# COMMUNICATION.net
KiCad netlist of a schematic drawn in Altium Designer
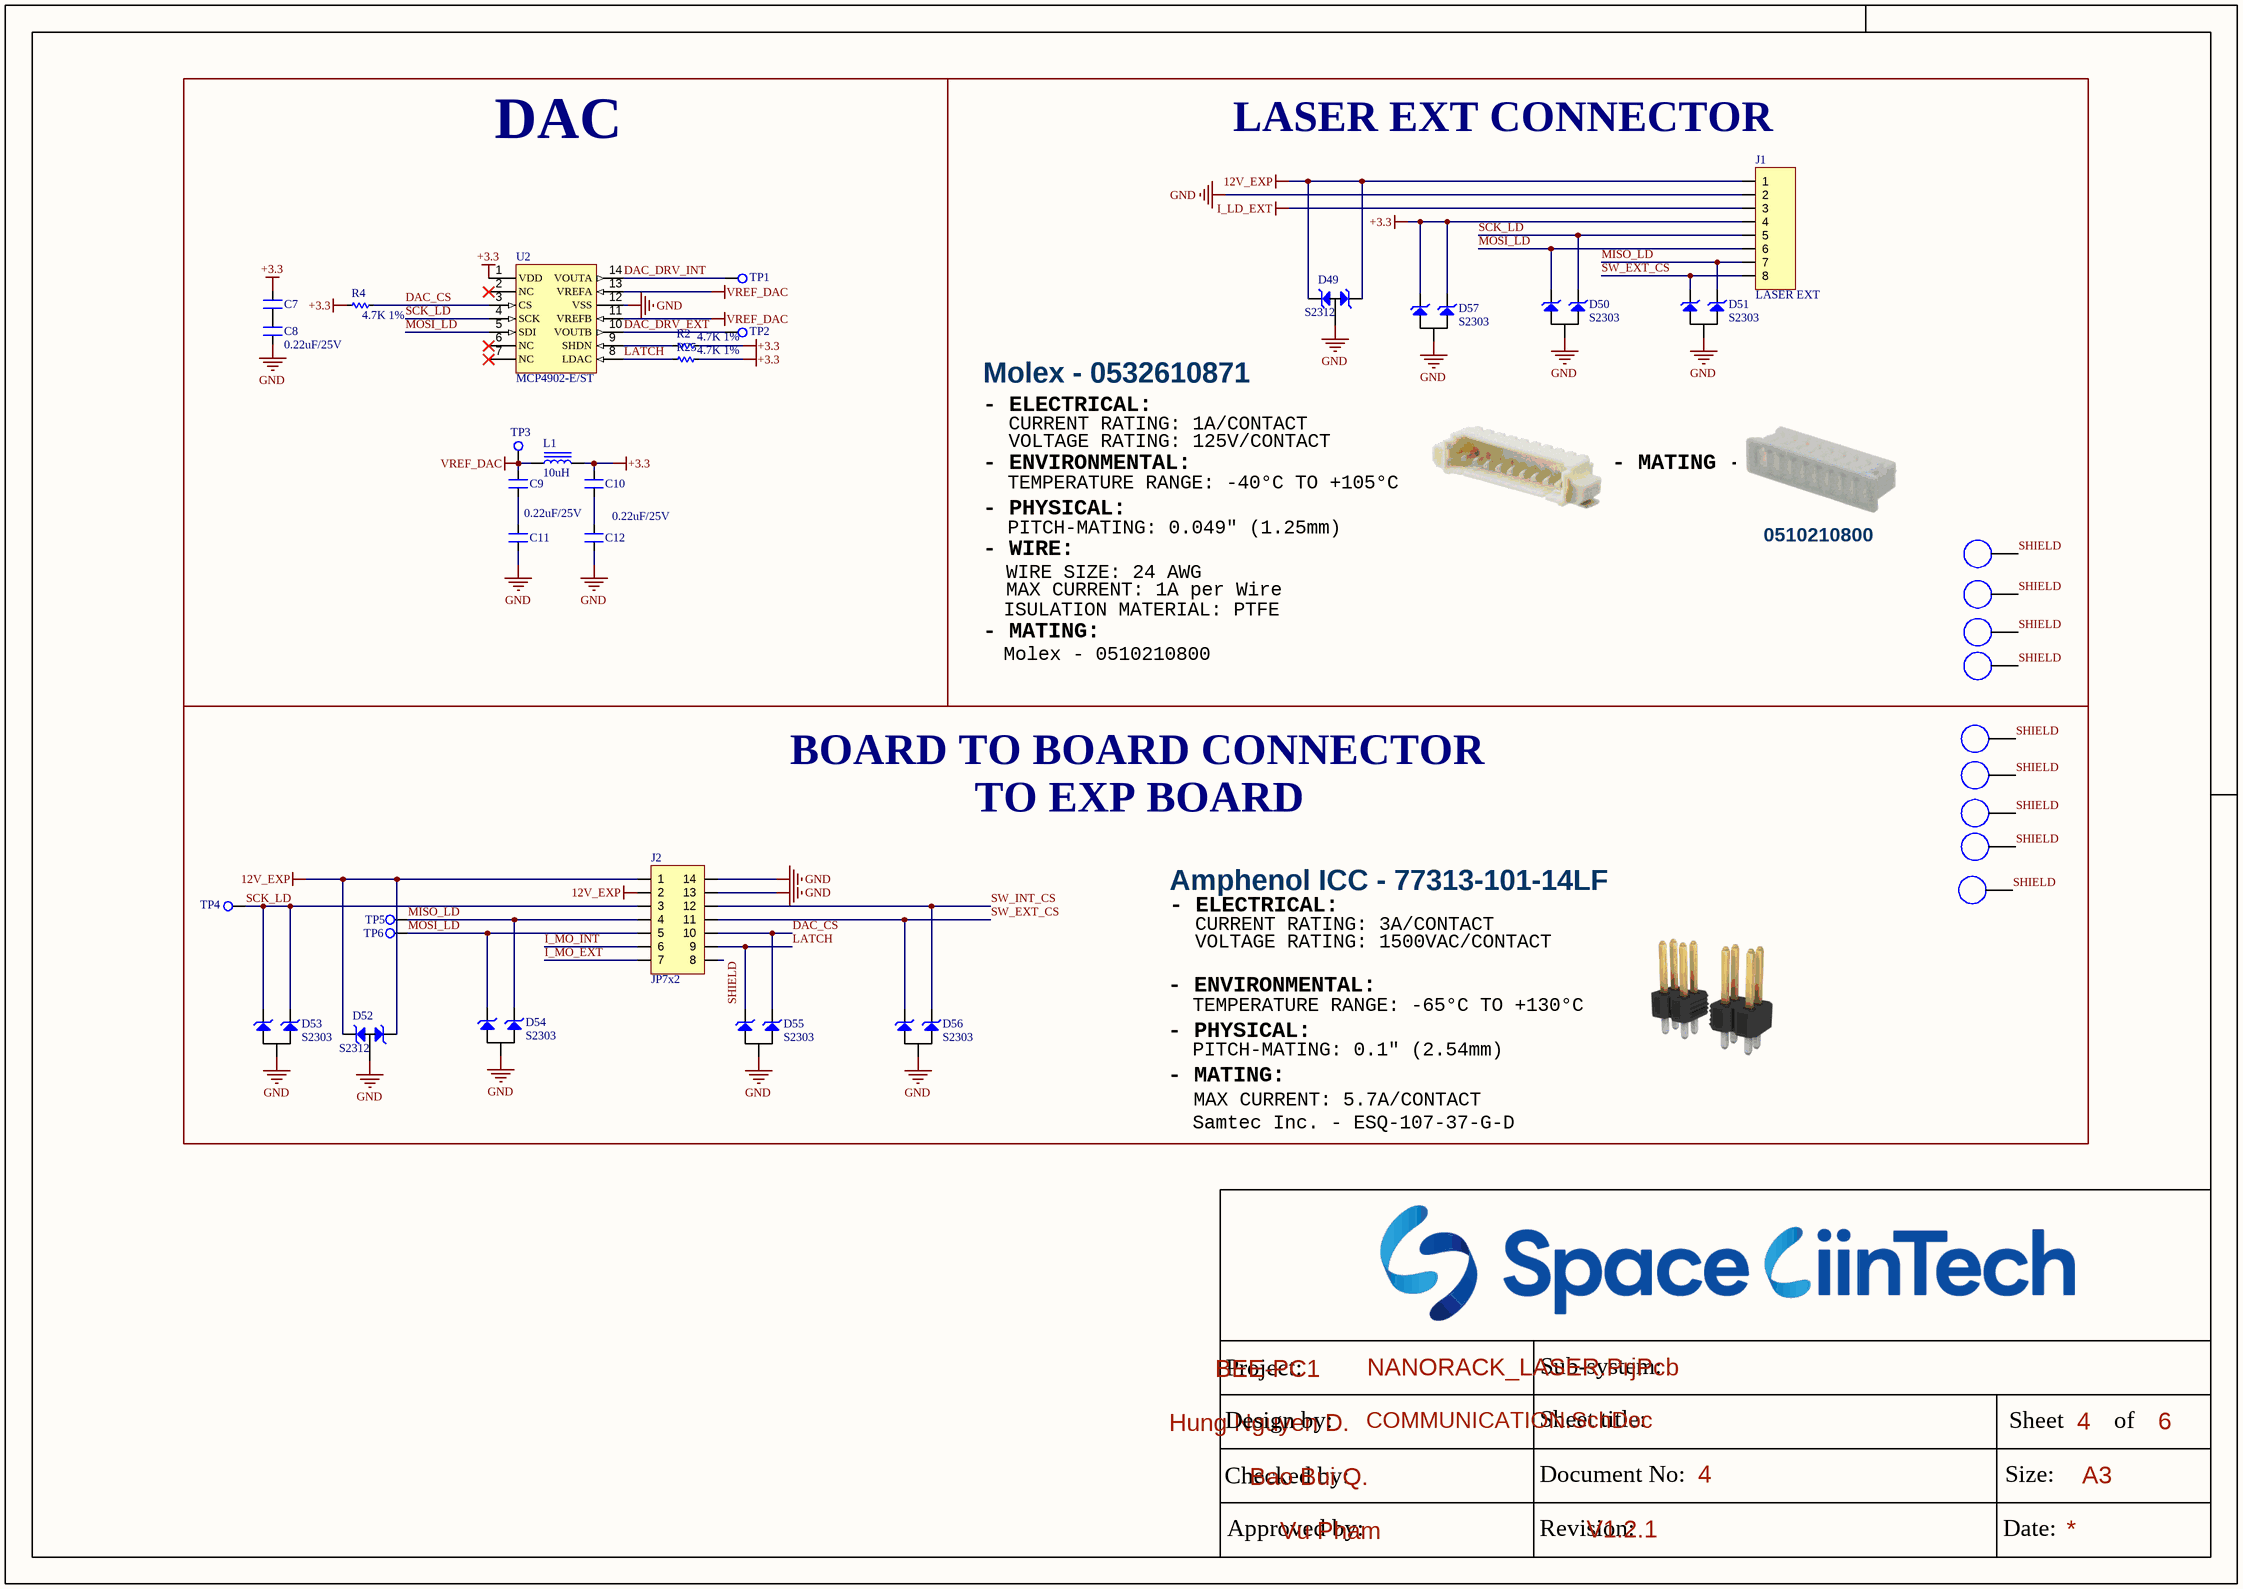
[diagram p0: COMMUNICATION.SchDoc]

(export (version "E")
  (design (tool "Eeschema 10.0.6"))
  (components
    (comp (ref "C7")
      (value "0.22uF/25V")
      (footprint "SM-0603")
      (description "0603")
      (libsource (lib "Capacitors") (part "CM"))
    )
    (comp (ref "C8")
      (value "0.22uF/25V")
      (footprint "SM-0603")
      (description "0603")
      (libsource (lib "Capacitors") (part "CM"))
    )
    (comp (ref "C9")
      (value "0.22uF/25V")
      (footprint "SM-0603")
      (description "0603")
      (libsource (lib "Capacitors") (part "CM"))
    )
    (comp (ref "C10")
      (value "0.22uF/25V")
      (footprint "SM-0603")
      (description "0603")
      (libsource (lib "Capacitors") (part "CM"))
    )
    (comp (ref "C11")
      (value "0.22uF/25V")
      (footprint "SM-0603")
      (description "0603")
      (libsource (lib "Capacitors") (part "CM"))
    )
    (comp (ref "C12")
      (value "0.22uF/25V")
      (footprint "SM-0603")
      (description "0603")
      (libsource (lib "Capacitors") (part "CM"))
    )
    (comp (ref "D49")
      (value "S2312")
      (footprint "SOT23-123")
      (description "TVS DIODE 12VWM 19VC SOT23, P/N:  S2312")
      (libsource (lib "Library") (part "S2315"))
    )
    (comp (ref "D50")
      (value "S2303")
      (footprint "SOT23-123")
      (description "TVS DIODE 3.3VWM 8VC SOT23, P/N:  \r\nS2303")
      (libsource (lib "Library") (part "S2303"))
    )
    (comp (ref "D51")
      (value "S2303")
      (footprint "SOT23-123")
      (description "TVS DIODE 3.3VWM 8VC SOT23, P/N:  \r\nS2303")
      (libsource (lib "Library") (part "S2303"))
    )
    (comp (ref "D52")
      (value "S2312")
      (footprint "SOT23-123")
      (description "TVS DIODE 12VWM 19VC SOT23, P/N:  S2312")
      (libsource (lib "Library") (part "S2315"))
    )
    (comp (ref "D53")
      (value "S2303")
      (footprint "SOT23-123")
      (description "TVS DIODE 3.3VWM 8VC SOT23, P/N:  \r\nS2303")
      (libsource (lib "Library") (part "S2303"))
    )
    (comp (ref "D54")
      (value "S2303")
      (footprint "SOT23-123")
      (description "TVS DIODE 3.3VWM 8VC SOT23, P/N:  \r\nS2303")
      (libsource (lib "Library") (part "S2303"))
    )
    (comp (ref "D55")
      (value "S2303")
      (footprint "SOT23-123")
      (description "TVS DIODE 3.3VWM 8VC SOT23, P/N:  \r\nS2303")
      (libsource (lib "Library") (part "S2303"))
    )
    (comp (ref "D56")
      (value "S2303")
      (footprint "SOT23-123")
      (description "TVS DIODE 3.3VWM 8VC SOT23, P/N:  \r\nS2303")
      (libsource (lib "Library") (part "S2303"))
    )
    (comp (ref "D57")
      (value "S2303")
      (footprint "SOT23-123")
      (description "TVS DIODE 3.3VWM 8VC SOT23, P/N:  \r\nS2303")
      (libsource (lib "Library") (part "S2303"))
    )
    (comp (ref "H1") (value "HOLD") (footprint "M3") (libsource (lib "Library_HUNG") (part "PAD_HOLD")))
    (comp (ref "H2") (value "HOLD") (footprint "M3") (libsource (lib "Library_HUNG") (part "PAD_HOLD")))
    (comp (ref "H3") (value "HOLD") (footprint "M3") (libsource (lib "Library_HUNG") (part "PAD_HOLD")))
    (comp (ref "H4") (value "HOLD") (footprint "M3") (libsource (lib "Library_HUNG") (part "PAD_HOLD")))
    (comp (ref "H5") (value "HOLD") (footprint "M3") (libsource (lib "Library_HUNG") (part "PAD_HOLD")))
    (comp (ref "H6") (value "HOLD") (footprint "M3") (libsource (lib "Library_HUNG") (part "PAD_HOLD")))
    (comp (ref "H7") (value "HOLD") (footprint "M3") (libsource (lib "Library_HUNG") (part "PAD_HOLD")))
    (comp (ref "H8") (value "HOLD") (footprint "M3") (libsource (lib "Library_HUNG") (part "PAD_HOLD")))
    (comp (ref "H9") (value "HOLD") (footprint "M3") (libsource (lib "Library_HUNG") (part "PAD_HOLD")))
    (comp (ref "J1")
      (value "LASER EXT")
      (footprint "0532610871")
      (description "WR-PHD 2.54 mm Angled Socket Header")
      (fields
        (field (name "MANUFACTURER") "Würth Elektronik eiSos GmbH")
        (field (name "PARTNO") "613008143121")
        (field (name "CREATED BY") "Karrer Zheng")
      )
      (libsource (lib "Library_HUNG") (part "JP8"))
    )
    (comp (ref "J2")
      (value "JP7x2")
      (footprint "JP7-D2T")
      (description "WR-PHD 2.54 mm Dual Socket Header")
      (fields
        (field (name "MANUFACTURER") "Würth Elektronik eiSos GmbH")
        (field (name "PARTNO") "61301421821")
        (field (name "CREATED BY") "Karrer Zheng")
      )
      (libsource (lib "Library") (part "JP7x2"))
    )
    (comp (ref "L1")
      (value "10uH")
      (footprint "FER 0805/2012")
      (description "MLZ1608N100LT000")
      (libsource (lib "INDUCTOR") (part "Inductor"))
    )
    (comp (ref "R2")
      (value "4.7K 1%")
      (footprint "RES-SMD-0603")
      (description "0603")
      (fields
        (field (name "MANUFACTURER") "Generic Components")
        (field (name "PUBLISHER") "Altium Hobart Technology Centre")
      )
      (libsource (lib "Library") (part "Res-SMD"))
    )
    (comp (ref "R4")
      (value "4.7K 1%")
      (footprint "RES-SMD-0603")
      (description "0603")
      (fields
        (field (name "MANUFACTURER") "Generic Components")
        (field (name "PUBLISHER") "Altium Hobart Technology Centre")
      )
      (libsource (lib "Library") (part "Res-SMD"))
    )
    (comp (ref "R25")
      (value "4.7K 1%")
      (footprint "RES-SMD-0603")
      (description "0603")
      (fields
        (field (name "MANUFACTURER") "Generic Components")
        (field (name "PUBLISHER") "Altium Hobart Technology Centre")
      )
      (libsource (lib "Library") (part "Res-SMD"))
    )
    (comp (ref "TP1")
      (value "Test_Point")
      (footprint "TESTPOINT")
      (libsource (lib "Library_HUNG") (part "Test_Point"))
    )
    (comp (ref "TP2")
      (value "Test_Point")
      (footprint "TESTPOINT")
      (libsource (lib "Library_HUNG") (part "Test_Point"))
    )
    (comp (ref "TP3")
      (value "Test_Point")
      (footprint "TESTPOINT")
      (libsource (lib "Library_HUNG") (part "Test_Point"))
    )
    (comp (ref "TP4")
      (value "Test_Point")
      (footprint "TESTPOINT")
      (libsource (lib "Library_HUNG") (part "Test_Point"))
    )
    (comp (ref "TP5")
      (value "Test_Point")
      (footprint "TESTPOINT")
      (libsource (lib "Library_HUNG") (part "Test_Point"))
    )
    (comp (ref "TP6")
      (value "Test_Point")
      (footprint "TESTPOINT")
      (libsource (lib "Library_HUNG") (part "Test_Point"))
    )
    (comp (ref "U2")
      (value "MCP4902-E/ST")
      (footprint "TSSOP14")
      (description "IC DAC 8BIT V-OUT 14TSSOP")
      (libsource (lib "Library") (part "MCP4902"))
    )
  )
  (nets
    (net (code "1") (name "+3.3") (class "Default")
      (node (ref "C10") (pin "2") (pinfunction "2_2") (pintype "passive"))
      (node (ref "C7") (pin "2") (pinfunction "2_2") (pintype "passive"))
      (node (ref "D57") (pin "1") (pintype "passive"))
      (node (ref "D57") (pin "3") (pintype "passive"))
      (node (ref "J1") (pin "4") (pinfunction "4_4") (pintype "passive"))
      (node (ref "L1") (pin "2") (pinfunction "2_2") (pintype "passive"))
      (node (ref "R2") (pin "1") (pinfunction "1_1") (pintype "passive"))
      (node (ref "R25") (pin "1") (pinfunction "1_1") (pintype "passive"))
      (node (ref "R4") (pin "2") (pinfunction "2_2") (pintype "passive"))
      (node (ref "U2") (pin "1") (pinfunction "VDD_1") (pintype "power_in"))
    )
    (net (code "2") (name "/DAC_CS") (class "Default")
      (node (ref "D55") (pin "3") (pintype "passive"))
      (node (ref "J2") (pin "10") (pinfunction "10_10") (pintype "passive"))
      (node (ref "R4") (pin "1") (pinfunction "1_1") (pintype "passive"))
      (node (ref "U2") (pin "3") (pinfunction "CS_3") (pintype "input"))
    )
    (net (code "3") (name "/DAC_DRV_EXT") (class "Default")
      (node (ref "TP2") (pin "1") (pintype "power_in"))
      (node (ref "U2") (pin "10") (pinfunction "VOUTB_10") (pintype "output"))
    )
    (net (code "4") (name "/DAC_DRV_INT") (class "Default")
      (node (ref "TP1") (pin "1") (pintype "power_in"))
      (node (ref "U2") (pin "14") (pinfunction "VOUTA_14") (pintype "output"))
    )
    (net (code "5") (name "/I_MO_EXT") (class "Default")
      (node (ref "J2") (pin "7") (pinfunction "7_7") (pintype "passive"))
    )
    (net (code "6") (name "/I_MO_INT") (class "Default")
      (node (ref "J2") (pin "6") (pinfunction "6_6") (pintype "passive"))
    )
    (net (code "7") (name "/LATCH") (class "Default")
      (node (ref "D55") (pin "1") (pintype "passive"))
      (node (ref "J2") (pin "9") (pinfunction "9_9") (pintype "passive"))
      (node (ref "R25") (pin "2") (pinfunction "2_2") (pintype "passive"))
      (node (ref "U2") (pin "8") (pinfunction "LDAC_8") (pintype "input"))
    )
    (net (code "8") (name "/MISO_LD") (class "Default")
      (node (ref "D51") (pin "3") (pintype "passive"))
      (node (ref "D54") (pin "3") (pintype "passive"))
      (node (ref "J1") (pin "7") (pinfunction "7_7") (pintype "passive"))
      (node (ref "J2") (pin "4") (pinfunction "4_4") (pintype "passive"))
      (node (ref "TP5") (pin "1") (pintype "power_in"))
    )
    (net (code "9") (name "/MOSI_LD") (class "Default")
      (node (ref "D50") (pin "1") (pintype "passive"))
      (node (ref "D54") (pin "1") (pintype "passive"))
      (node (ref "J1") (pin "6") (pinfunction "6_6") (pintype "passive"))
      (node (ref "J2") (pin "5") (pinfunction "5_5") (pintype "passive"))
      (node (ref "TP6") (pin "1") (pintype "power_in"))
      (node (ref "U2") (pin "5") (pinfunction "SDI_5") (pintype "input"))
    )
    (net (code "10") (name "/SCK_LD") (class "Default")
      (node (ref "D50") (pin "3") (pintype "passive"))
      (node (ref "D53") (pin "1") (pintype "passive"))
      (node (ref "D53") (pin "3") (pintype "passive"))
      (node (ref "J1") (pin "5") (pinfunction "5_5") (pintype "passive"))
      (node (ref "J2") (pin "3") (pinfunction "3_3") (pintype "passive"))
      (node (ref "TP4") (pin "1") (pintype "power_in"))
      (node (ref "U2") (pin "4") (pinfunction "SCK_4") (pintype "input"))
    )
    (net (code "11") (name "/SHIELD") (class "Default")
      (node (ref "H1") (pin "1") (pintype "power_in"))
      (node (ref "H2") (pin "1") (pintype "power_in"))
      (node (ref "H3") (pin "1") (pintype "power_in"))
      (node (ref "H4") (pin "1") (pintype "power_in"))
      (node (ref "H5") (pin "1") (pintype "power_in"))
      (node (ref "H6") (pin "1") (pintype "power_in"))
      (node (ref "H7") (pin "1") (pintype "power_in"))
      (node (ref "H8") (pin "1") (pintype "power_in"))
      (node (ref "H9") (pin "1") (pintype "power_in"))
      (node (ref "J2") (pin "8") (pinfunction "8_8") (pintype "passive"))
    )
    (net (code "12") (name "/SW_EXT_CS") (class "Default")
      (node (ref "D51") (pin "1") (pintype "passive"))
      (node (ref "D56") (pin "1") (pintype "passive"))
      (node (ref "J1") (pin "8") (pinfunction "8_8") (pintype "passive"))
      (node (ref "J2") (pin "11") (pinfunction "11_11") (pintype "passive"))
    )
    (net (code "13") (name "/SW_INT_CS") (class "Default")
      (node (ref "D56") (pin "3") (pintype "passive"))
      (node (ref "J2") (pin "12") (pinfunction "12_12") (pintype "passive"))
    )
    (net (code "14") (name "12V_EXP") (class "Default")
      (node (ref "D49") (pin "1") (pintype "passive"))
      (node (ref "D49") (pin "3") (pintype "passive"))
      (node (ref "D52") (pin "1") (pintype "passive"))
      (node (ref "D52") (pin "3") (pintype "passive"))
      (node (ref "J1") (pin "1") (pinfunction "1_1") (pintype "passive"))
      (node (ref "J2") (pin "1") (pinfunction "1_1") (pintype "passive"))
      (node (ref "J2") (pin "2") (pinfunction "2_2") (pintype "passive"))
    )
    (net (code "15") (name "GND") (class "Default")
      (node (ref "C11") (pin "1") (pinfunction "1_1") (pintype "passive"))
      (node (ref "C12") (pin "1") (pinfunction "1_1") (pintype "passive"))
      (node (ref "C8") (pin "1") (pinfunction "1_1") (pintype "passive"))
      (node (ref "D49") (pin "2") (pintype "passive"))
      (node (ref "D50") (pin "2") (pintype "passive"))
      (node (ref "D51") (pin "2") (pintype "passive"))
      (node (ref "D52") (pin "2") (pintype "passive"))
      (node (ref "D53") (pin "2") (pintype "passive"))
      (node (ref "D54") (pin "2") (pintype "passive"))
      (node (ref "D55") (pin "2") (pintype "passive"))
      (node (ref "D56") (pin "2") (pintype "passive"))
      (node (ref "D57") (pin "2") (pintype "passive"))
      (node (ref "J1") (pin "2") (pinfunction "2_2") (pintype "passive"))
      (node (ref "J2") (pin "13") (pinfunction "13_13") (pintype "passive"))
      (node (ref "J2") (pin "14") (pinfunction "14_14") (pintype "passive"))
      (node (ref "U2") (pin "12") (pinfunction "VSS_12") (pintype "power_in"))
    )
    (net (code "16") (name "I_LD_EXT") (class "Default")
      (node (ref "J1") (pin "3") (pinfunction "3_3") (pintype "passive"))
    )
    (net (code "17") (name "Net-(C7-Pad1)") (class "Default")
      (node (ref "C7") (pin "1") (pinfunction "1_1") (pintype "passive"))
      (node (ref "C8") (pin "2") (pinfunction "2_2") (pintype "passive"))
    )
    (net (code "18") (name "Net-(C10-Pad1)") (class "Default")
      (node (ref "C10") (pin "1") (pinfunction "1_1") (pintype "passive"))
      (node (ref "C12") (pin "2") (pinfunction "2_2") (pintype "passive"))
    )
    (net (code "19") (name "Net-(C11-Pad2)") (class "Default")
      (node (ref "C11") (pin "2") (pinfunction "2_2") (pintype "passive"))
      (node (ref "C9") (pin "1") (pinfunction "1_1") (pintype "passive"))
    )
    (net (code "20") (name "Net-(U2-SHDN)") (class "Default")
      (node (ref "R2") (pin "2") (pinfunction "2_2") (pintype "passive"))
      (node (ref "U2") (pin "9") (pinfunction "SHDN_9") (pintype "input"))
    )
    (net (code "21") (name "VREF_DAC") (class "Default")
      (node (ref "C9") (pin "2") (pinfunction "2_2") (pintype "passive"))
      (node (ref "L1") (pin "1") (pinfunction "1_1") (pintype "passive"))
      (node (ref "TP3") (pin "1") (pintype "power_in"))
      (node (ref "U2") (pin "11") (pinfunction "VREFB_11") (pintype "input"))
      (node (ref "U2") (pin "13") (pinfunction "VREFA_13") (pintype "input"))
    )
    (net (code "22") (name "unconnected-(U2-NC-Pad2)") (class "Default")
      (node (ref "U2") (pin "2") (pinfunction "NC_2") (pintype "tri_state+no_connect"))
    )
    (net (code "23") (name "unconnected-(U2-NC-Pad6)") (class "Default")
      (node (ref "U2") (pin "6") (pinfunction "NC_6") (pintype "tri_state+no_connect"))
    )
    (net (code "24") (name "unconnected-(U2-NC-Pad7)") (class "Default")
      (node (ref "U2") (pin "7") (pinfunction "NC_7") (pintype "tri_state+no_connect"))
    )
  )
)
